# TRX.net
KiCad netlist of a schematic drawn in Altium Designer
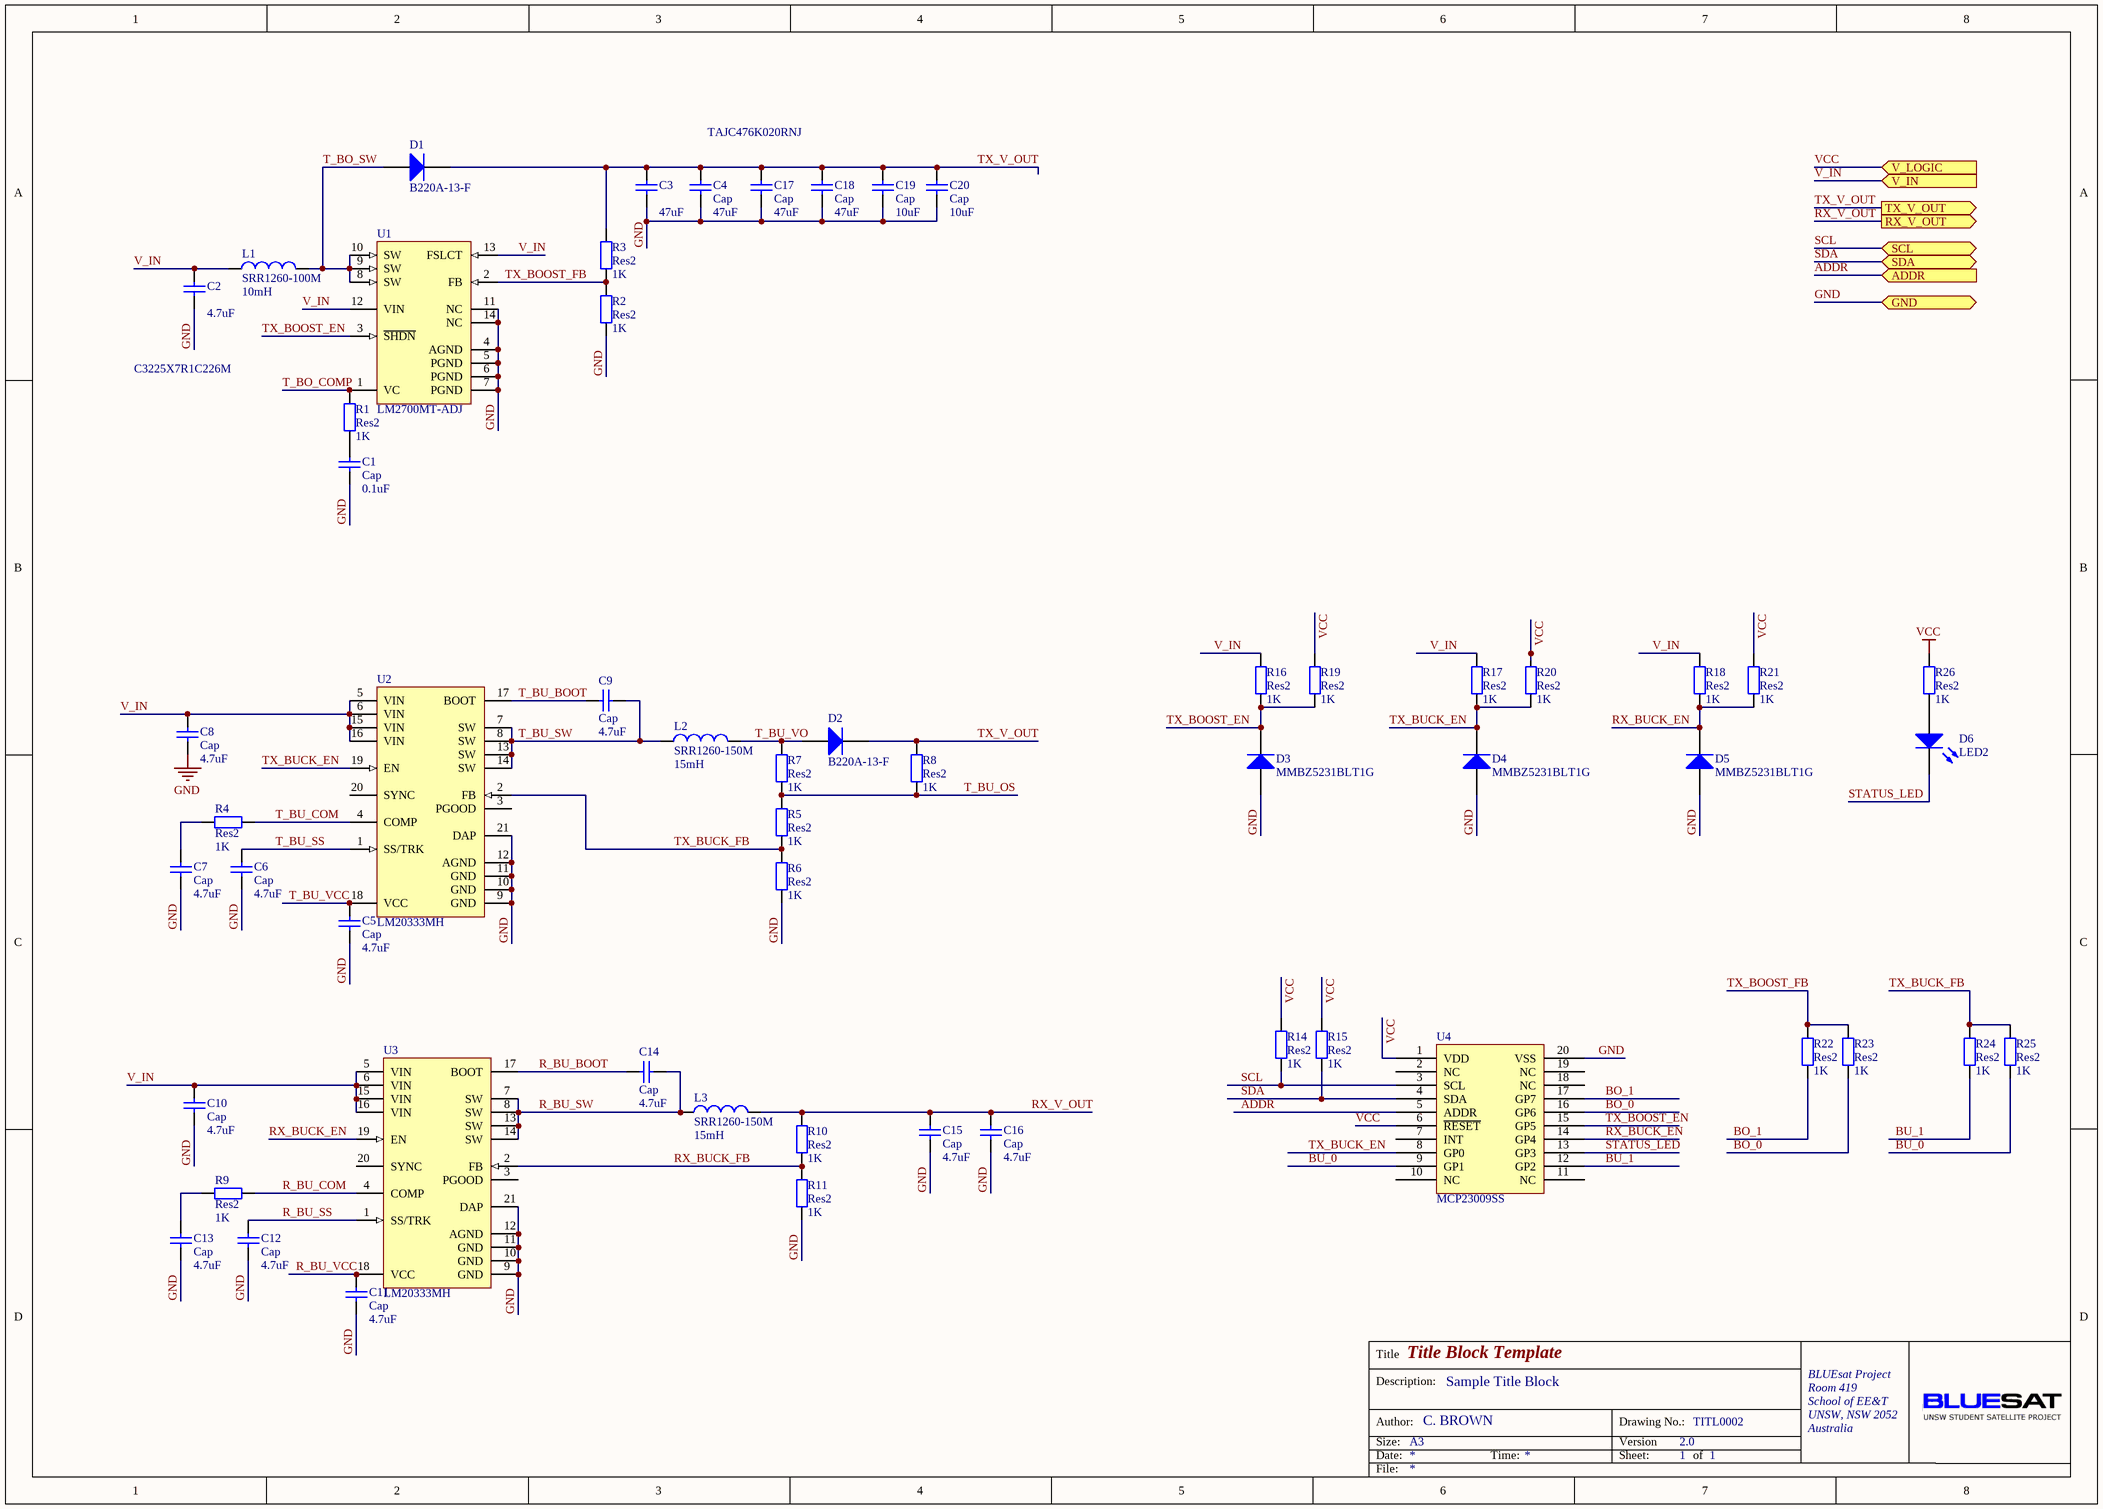
[diagram p0: TRX.SchDoc]

(export (version "E")
  (design (tool "Eeschema 10.0.6"))
  (components
    (comp (ref "C1")
      (value "Cap")
      (footprint "R0805M")
      (description "Capacitor")
      (fields (field (name "ALTIUM_VALUE") "0.1uF") (field (name "PUBLISHER") "Altium Limited"))
      (libsource (lib "Miscellaneous Devices") (part "Cap"))
    )
    (comp (ref "C2")
      (value "C3225X7R1C226M")
      (footprint "R1210M")
      (description "Capacitor")
      (fields (field (name "ALTIUM_VALUE") "4.7uF") (field (name "PUBLISHER") "Altium Limited"))
      (libsource (lib "Miscellaneous Devices") (part "Cap"))
    )
    (comp (ref "C3")
      (value "TAJC476K020RNJ")
      (footprint "TANTCASEC")
      (description "Capacitor")
      (fields (field (name "ALTIUM_VALUE") "47uF") (field (name "PUBLISHER") "Altium Limited"))
      (libsource (lib "Miscellaneous Devices") (part "Cap"))
    )
    (comp (ref "C4")
      (value "Cap")
      (footprint "TANTCASEC")
      (description "Capacitor")
      (fields (field (name "ALTIUM_VALUE") "47uF") (field (name "PUBLISHER") "Altium Limited"))
      (libsource (lib "Miscellaneous Devices") (part "Cap"))
    )
    (comp (ref "C5")
      (value "Cap")
      (footprint "R0805M")
      (description "Capacitor")
      (fields (field (name "ALTIUM_VALUE") "4.7uF") (field (name "PUBLISHER") "Altium Limited"))
      (libsource (lib "Miscellaneous Devices") (part "Cap"))
    )
    (comp (ref "C6")
      (value "Cap")
      (footprint "R0805M")
      (description "Capacitor")
      (fields (field (name "ALTIUM_VALUE") "4.7uF") (field (name "PUBLISHER") "Altium Limited"))
      (libsource (lib "Miscellaneous Devices") (part "Cap"))
    )
    (comp (ref "C7")
      (value "Cap")
      (footprint "R0805M")
      (description "Capacitor")
      (fields (field (name "ALTIUM_VALUE") "4.7uF") (field (name "PUBLISHER") "Altium Limited"))
      (libsource (lib "Miscellaneous Devices") (part "Cap"))
    )
    (comp (ref "C8")
      (value "Cap")
      (footprint "R1210M")
      (description "Capacitor")
      (fields (field (name "ALTIUM_VALUE") "4.7uF") (field (name "PUBLISHER") "Altium Limited"))
      (libsource (lib "Miscellaneous Devices") (part "Cap"))
    )
    (comp (ref "C9")
      (value "Cap")
      (footprint "R0805M")
      (description "Capacitor")
      (fields (field (name "ALTIUM_VALUE") "4.7uF") (field (name "PUBLISHER") "Altium Limited"))
      (libsource (lib "Miscellaneous Devices") (part "Cap"))
    )
    (comp (ref "C10")
      (value "Cap")
      (footprint "R1210M")
      (description "Capacitor")
      (fields (field (name "ALTIUM_VALUE") "4.7uF") (field (name "PUBLISHER") "Altium Limited"))
      (libsource (lib "Miscellaneous Devices") (part "Cap"))
    )
    (comp (ref "C11")
      (value "Cap")
      (footprint "R0805M")
      (description "Capacitor")
      (fields (field (name "ALTIUM_VALUE") "4.7uF") (field (name "PUBLISHER") "Altium Limited"))
      (libsource (lib "Miscellaneous Devices") (part "Cap"))
    )
    (comp (ref "C12")
      (value "Cap")
      (footprint "R0805M")
      (description "Capacitor")
      (fields (field (name "ALTIUM_VALUE") "4.7uF") (field (name "PUBLISHER") "Altium Limited"))
      (libsource (lib "Miscellaneous Devices") (part "Cap"))
    )
    (comp (ref "C13")
      (value "Cap")
      (footprint "R0805M")
      (description "Capacitor")
      (fields (field (name "ALTIUM_VALUE") "4.7uF") (field (name "PUBLISHER") "Altium Limited"))
      (libsource (lib "Miscellaneous Devices") (part "Cap"))
    )
    (comp (ref "C14")
      (value "Cap")
      (footprint "R0805M")
      (description "Capacitor")
      (fields (field (name "ALTIUM_VALUE") "4.7uF") (field (name "PUBLISHER") "Altium Limited"))
      (libsource (lib "Miscellaneous Devices") (part "Cap"))
    )
    (comp (ref "C15")
      (value "Cap")
      (footprint "R0805M")
      (description "Capacitor")
      (fields (field (name "ALTIUM_VALUE") "4.7uF") (field (name "PUBLISHER") "Altium Limited"))
      (libsource (lib "Miscellaneous Devices") (part "Cap"))
    )
    (comp (ref "C16")
      (value "Cap")
      (footprint "R0805M")
      (description "Capacitor")
      (fields (field (name "ALTIUM_VALUE") "4.7uF") (field (name "PUBLISHER") "Altium Limited"))
      (libsource (lib "Miscellaneous Devices") (part "Cap"))
    )
    (comp (ref "C17")
      (value "Cap")
      (footprint "TANTCASEC")
      (description "Capacitor")
      (fields (field (name "ALTIUM_VALUE") "47uF") (field (name "PUBLISHER") "Altium Limited"))
      (libsource (lib "Miscellaneous Devices") (part "Cap"))
    )
    (comp (ref "C18")
      (value "Cap")
      (footprint "TANTCASEC")
      (description "Capacitor")
      (fields (field (name "ALTIUM_VALUE") "47uF") (field (name "PUBLISHER") "Altium Limited"))
      (libsource (lib "Miscellaneous Devices") (part "Cap"))
    )
    (comp (ref "C19")
      (value "Cap")
      (footprint "R0805M")
      (description "Capacitor")
      (fields (field (name "ALTIUM_VALUE") "10uF") (field (name "PUBLISHER") "Altium Limited"))
      (libsource (lib "Miscellaneous Devices") (part "Cap"))
    )
    (comp (ref "C20")
      (value "Cap")
      (footprint "R0805M")
      (description "Capacitor")
      (fields (field (name "ALTIUM_VALUE") "10uF") (field (name "PUBLISHER") "Altium Limited"))
      (libsource (lib "Miscellaneous Devices") (part "Cap"))
    )
    (comp (ref "D1")
      (value "B220A-13-F")
      (footprint "DIODESMA")
      (description "High Conductance Fast Diode")
      (fields (field (name "PUBLISHER") "Altium Limited"))
      (libsource (lib "Miscellaneous Devices") (part "Diode 1N4148"))
    )
    (comp (ref "D2")
      (value "B220A-13-F")
      (footprint "DIODESMA")
      (description "High Conductance Fast Diode")
      (fields (field (name "PUBLISHER") "Altium Limited"))
      (libsource (lib "Miscellaneous Devices") (part "Diode 1N4148"))
    )
    (comp (ref "D3")
      (value "MMBZ5231BLT1G")
      (footprint "SOT95P240-3N")
      (description "Silicon Switching Diode for High-Speed Switching")
      (fields (field (name "PUBLISHER") "Altium Limited"))
      (libsource (lib "Miscellaneous Devices") (part "Diode BAS16"))
    )
    (comp (ref "D4")
      (value "MMBZ5231BLT1G")
      (footprint "SOT95P240-3N")
      (description "Silicon Switching Diode for High-Speed Switching")
      (fields (field (name "PUBLISHER") "Altium Limited"))
      (libsource (lib "Miscellaneous Devices") (part "Diode BAS16"))
    )
    (comp (ref "D5")
      (value "MMBZ5231BLT1G")
      (footprint "SOT95P240-3N")
      (description "Silicon Switching Diode for High-Speed Switching")
      (fields (field (name "PUBLISHER") "Altium Limited"))
      (libsource (lib "Miscellaneous Devices") (part "Diode BAS16"))
    )
    (comp (ref "D6")
      (value "LED2")
      (footprint "R0805M")
      (description "Typical RED, GREEN, YELLOW, AMBER GaAs LED")
      (fields (field (name "PUBLISHER") "Altium Limited"))
      (libsource (lib "Miscellaneous Devices") (part "LED2"))
    )
    (comp (ref "L1")
      (value "SRR1260-100M")
      (footprint "SRR1260M")
      (description "Inductor")
      (fields (field (name "ALTIUM_VALUE") "10mH") (field (name "PUBLISHER") "Altium Limited"))
      (libsource (lib "Miscellaneous Devices") (part "Inductor"))
    )
    (comp (ref "L2")
      (value "SRR1260-150M")
      (footprint "SRR1260M")
      (description "Inductor")
      (fields (field (name "ALTIUM_VALUE") "15mH") (field (name "PUBLISHER") "Altium Limited"))
      (libsource (lib "Miscellaneous Devices") (part "Inductor"))
    )
    (comp (ref "L3")
      (value "SRR1260-150M")
      (footprint "SRR1260M")
      (description "Inductor")
      (fields (field (name "ALTIUM_VALUE") "15mH") (field (name "PUBLISHER") "Altium Limited"))
      (libsource (lib "Miscellaneous Devices") (part "Inductor"))
    )
    (comp (ref "R1")
      (value "Res2")
      (footprint "R0805M")
      (description "Resistor")
      (fields (field (name "ALTIUM_VALUE") "1K") (field (name "PUBLISHER") "Altium Limited"))
      (libsource (lib "") (part "Res2_1"))
    )
    (comp (ref "R2")
      (value "Res2")
      (footprint "R0805M")
      (description "Resistor")
      (fields (field (name "ALTIUM_VALUE") "1K") (field (name "PUBLISHER") "Altium Limited"))
      (libsource (lib "") (part "Res2_1"))
    )
    (comp (ref "R3")
      (value "Res2")
      (footprint "R0805M")
      (description "Resistor")
      (fields (field (name "ALTIUM_VALUE") "1K") (field (name "PUBLISHER") "Altium Limited"))
      (libsource (lib "") (part "Res2_1"))
    )
    (comp (ref "R4")
      (value "Res2")
      (footprint "R0805M")
      (description "Resistor")
      (fields (field (name "ALTIUM_VALUE") "1K") (field (name "PUBLISHER") "Altium Limited"))
      (libsource (lib "") (part "Res2_2"))
    )
    (comp (ref "R5")
      (value "Res2")
      (footprint "R0805M")
      (description "Resistor")
      (fields (field (name "ALTIUM_VALUE") "1K") (field (name "PUBLISHER") "Altium Limited"))
      (libsource (lib "Miscellaneous Devices") (part "Res2"))
    )
    (comp (ref "R6")
      (value "Res2")
      (footprint "R0805M")
      (description "Resistor")
      (fields (field (name "ALTIUM_VALUE") "1K") (field (name "PUBLISHER") "Altium Limited"))
      (libsource (lib "Miscellaneous Devices") (part "Res2"))
    )
    (comp (ref "R7")
      (value "Res2")
      (footprint "R0805M")
      (description "Resistor")
      (fields (field (name "ALTIUM_VALUE") "1K") (field (name "PUBLISHER") "Altium Limited"))
      (libsource (lib "Miscellaneous Devices") (part "Res2"))
    )
    (comp (ref "R8")
      (value "Res2")
      (footprint "R0805M")
      (description "Resistor")
      (fields (field (name "ALTIUM_VALUE") "1K") (field (name "PUBLISHER") "Altium Limited"))
      (libsource (lib "Miscellaneous Devices") (part "Res2"))
    )
    (comp (ref "R9")
      (value "Res2")
      (footprint "R0805M")
      (description "Resistor")
      (fields (field (name "ALTIUM_VALUE") "1K") (field (name "PUBLISHER") "Altium Limited"))
      (libsource (lib "") (part "Res2_2"))
    )
    (comp (ref "R10")
      (value "Res2")
      (footprint "R0805M")
      (description "Resistor")
      (fields (field (name "ALTIUM_VALUE") "1K") (field (name "PUBLISHER") "Altium Limited"))
      (libsource (lib "") (part "Res2_1"))
    )
    (comp (ref "R11")
      (value "Res2")
      (footprint "R0805M")
      (description "Resistor")
      (fields (field (name "ALTIUM_VALUE") "1K") (field (name "PUBLISHER") "Altium Limited"))
      (libsource (lib "") (part "Res2_1"))
    )
    (comp (ref "R14")
      (value "Res2")
      (footprint "R0805M")
      (description "Resistor")
      (fields (field (name "ALTIUM_VALUE") "1K") (field (name "PUBLISHER") "Altium Limited"))
      (libsource (lib "") (part "Res2_1"))
    )
    (comp (ref "R15")
      (value "Res2")
      (footprint "R0805M")
      (description "Resistor")
      (fields (field (name "ALTIUM_VALUE") "1K") (field (name "PUBLISHER") "Altium Limited"))
      (libsource (lib "") (part "Res2_1"))
    )
    (comp (ref "R16")
      (value "Res2")
      (footprint "R0805M")
      (description "Resistor")
      (fields (field (name "ALTIUM_VALUE") "1K") (field (name "PUBLISHER") "Altium Limited"))
      (libsource (lib "") (part "Res2_1"))
    )
    (comp (ref "R17")
      (value "Res2")
      (footprint "R0805M")
      (description "Resistor")
      (fields (field (name "ALTIUM_VALUE") "1K") (field (name "PUBLISHER") "Altium Limited"))
      (libsource (lib "") (part "Res2_1"))
    )
    (comp (ref "R18")
      (value "Res2")
      (footprint "R0805M")
      (description "Resistor")
      (fields (field (name "ALTIUM_VALUE") "1K") (field (name "PUBLISHER") "Altium Limited"))
      (libsource (lib "") (part "Res2_1"))
    )
    (comp (ref "R19")
      (value "Res2")
      (footprint "R0805M")
      (description "Resistor")
      (fields (field (name "ALTIUM_VALUE") "1K") (field (name "PUBLISHER") "Altium Limited"))
      (libsource (lib "") (part "Res2_1"))
    )
    (comp (ref "R20")
      (value "Res2")
      (footprint "R0805M")
      (description "Resistor")
      (fields (field (name "ALTIUM_VALUE") "1K") (field (name "PUBLISHER") "Altium Limited"))
      (libsource (lib "") (part "Res2_1"))
    )
    (comp (ref "R21")
      (value "Res2")
      (footprint "R0805M")
      (description "Resistor")
      (fields (field (name "ALTIUM_VALUE") "1K") (field (name "PUBLISHER") "Altium Limited"))
      (libsource (lib "") (part "Res2_1"))
    )
    (comp (ref "R22")
      (value "Res2")
      (footprint "R0805M")
      (description "Resistor")
      (fields (field (name "ALTIUM_VALUE") "1K") (field (name "PUBLISHER") "Altium Limited"))
      (libsource (lib "") (part "Res2_1"))
    )
    (comp (ref "R23")
      (value "Res2")
      (footprint "R0805M")
      (description "Resistor")
      (fields (field (name "ALTIUM_VALUE") "1K") (field (name "PUBLISHER") "Altium Limited"))
      (libsource (lib "") (part "Res2_1"))
    )
    (comp (ref "R24")
      (value "Res2")
      (footprint "R0805M")
      (description "Resistor")
      (fields (field (name "ALTIUM_VALUE") "1K") (field (name "PUBLISHER") "Altium Limited"))
      (libsource (lib "") (part "Res2_1"))
    )
    (comp (ref "R25")
      (value "Res2")
      (footprint "R0805M")
      (description "Resistor")
      (fields (field (name "ALTIUM_VALUE") "1K") (field (name "PUBLISHER") "Altium Limited"))
      (libsource (lib "") (part "Res2_1"))
    )
    (comp (ref "R26")
      (value "Res2")
      (footprint "R0805M")
      (description "Resistor")
      (fields (field (name "ALTIUM_VALUE") "1K") (field (name "PUBLISHER") "Altium Limited"))
      (libsource (lib "") (part "Res2_1"))
    )
    (comp (ref "U1")
      (value "LM2700MT-ADJ")
      (footprint "MTC14_N")
      (description "600kHz/1.25MHz, 2.5A, Step-up PWM DC/DC Converter")
      (fields
        (field (name "MANUFACTURER") "National Semiconductor")
        (field (name "DIGIKEYPARTNUMBER") "LM2700MT-ADJ-ND")
        (field (name "PUBLISHER") "Altium Limited")
      )
      (libsource (lib "NSC Switcher") (part "LM2700MT-ADJ"))
    )
    (comp (ref "U2")
      (value "LM20333MH")
      (footprint "MXA20A_N")
      (description "36V, 3A PowerWise Synchronous Buck Regulator with Frequency Synchronization")
      (fields
        (field (name "MANUFACTURER") "National Semiconductor")
        (field (name "DIGIKEYPARTNUMBER") "LM20333MH-ND")
        (field (name "PUBLISHER") "Altium Limited")
      )
      (libsource (lib "NSC Switcher") (part "LM20333MH"))
    )
    (comp (ref "U3")
      (value "LM20333MH")
      (footprint "MXA20A_N")
      (description "36V, 3A PowerWise Synchronous Buck Regulator with Frequency Synchronization")
      (fields
        (field (name "MANUFACTURER") "National Semiconductor")
        (field (name "DIGIKEYPARTNUMBER") "LM20333MH-ND")
        (field (name "PUBLISHER") "Altium Limited")
      )
      (libsource (lib "NSC Switcher") (part "LM20333MH"))
    )
    (comp (ref "U4")
      (value "MCP23009SS")
      (footprint "SSOP-SS20_M")
      (libsource (lib "VarReg") (part "MCP23009SS"))
    )
  )
  (nets
    (net (code "1") (name "/ADDR") (class "Default")
      (node (ref "U4") (pin "5") (pinfunction "ADDR_5") (pintype "passive"))
    )
    (net (code "2") (name "/BO_0") (class "Default")
      (node (ref "R23") (pin "1") (pinfunction "1_1") (pintype "passive"))
      (node (ref "U4") (pin "16") (pinfunction "GP6_16") (pintype "passive"))
    )
    (net (code "3") (name "/BO_1") (class "Default")
      (node (ref "R22") (pin "1") (pinfunction "1_1") (pintype "passive"))
      (node (ref "U4") (pin "17") (pinfunction "GP7_17") (pintype "passive"))
    )
    (net (code "4") (name "/BU_0") (class "Default")
      (node (ref "R25") (pin "1") (pinfunction "1_1") (pintype "passive"))
      (node (ref "U4") (pin "9") (pinfunction "GP1_9") (pintype "passive"))
    )
    (net (code "5") (name "/BU_1") (class "Default")
      (node (ref "R24") (pin "1") (pinfunction "1_1") (pintype "passive"))
      (node (ref "U4") (pin "12") (pinfunction "GP2_12") (pintype "passive"))
    )
    (net (code "6") (name "/RX_BUCK_EN") (class "Default")
      (node (ref "D5") (pin "3") (pinfunction "K_3") (pintype "passive"))
      (node (ref "R18") (pin "1") (pinfunction "1_1") (pintype "passive"))
      (node (ref "R21") (pin "1") (pinfunction "1_1") (pintype "passive"))
      (node (ref "U3") (pin "19") (pinfunction "EN_19") (pintype "input"))
      (node (ref "U4") (pin "14") (pinfunction "GP4_14") (pintype "passive"))
    )
    (net (code "7") (name "/RX_BUCK_FB") (class "Default")
      (node (ref "R10") (pin "1") (pinfunction "1_1") (pintype "passive"))
      (node (ref "R11") (pin "2") (pinfunction "2_2") (pintype "passive"))
      (node (ref "U3") (pin "2") (pinfunction "FB_2") (pintype "input"))
    )
    (net (code "8") (name "/RX_V_OUT") (class "Default")
      (node (ref "C15") (pin "2") (pinfunction "2_2") (pintype "passive"))
      (node (ref "C16") (pin "2") (pinfunction "2_2") (pintype "passive"))
      (node (ref "L3") (pin "2") (pinfunction "2_2") (pintype "passive"))
      (node (ref "R10") (pin "2") (pinfunction "2_2") (pintype "passive"))
    )
    (net (code "9") (name "/R_BU_BOOT") (class "Default")
      (node (ref "C14") (pin "1") (pinfunction "1_1") (pintype "passive"))
      (node (ref "U3") (pin "17") (pinfunction "BOOT_17") (pintype "passive"))
    )
    (net (code "10") (name "/R_BU_COM") (class "Default")
      (node (ref "R9") (pin "1") (pinfunction "1_1") (pintype "passive"))
      (node (ref "U3") (pin "4") (pinfunction "COMP_4") (pintype "passive"))
    )
    (net (code "11") (name "/R_BU_SS") (class "Default")
      (node (ref "C12") (pin "2") (pinfunction "2_2") (pintype "passive"))
      (node (ref "U3") (pin "1") (pinfunction "SS/TRK_1") (pintype "input"))
    )
    (net (code "12") (name "/R_BU_SW") (class "Default")
      (node (ref "C14") (pin "2") (pinfunction "2_2") (pintype "passive"))
      (node (ref "L3") (pin "1") (pinfunction "1_1") (pintype "passive"))
      (node (ref "U3") (pin "13") (pinfunction "SW_13") (pintype "power_in"))
      (node (ref "U3") (pin "14") (pinfunction "SW_14") (pintype "power_in"))
      (node (ref "U3") (pin "7") (pinfunction "SW_7") (pintype "power_in"))
      (node (ref "U3") (pin "8") (pinfunction "SW_8") (pintype "power_in"))
    )
    (net (code "13") (name "/R_BU_VCC") (class "Default")
      (node (ref "C11") (pin "2") (pinfunction "2_2") (pintype "passive"))
      (node (ref "U3") (pin "18") (pinfunction "VCC_18") (pintype "power_in"))
    )
    (net (code "14") (name "/SCL") (class "Default")
      (node (ref "R14") (pin "1") (pinfunction "1_1") (pintype "passive"))
      (node (ref "U4") (pin "3") (pinfunction "SCL_3") (pintype "passive"))
    )
    (net (code "15") (name "/SDA") (class "Default")
      (node (ref "R15") (pin "1") (pinfunction "1_1") (pintype "passive"))
      (node (ref "U4") (pin "4") (pinfunction "SDA_4") (pintype "passive"))
    )
    (net (code "16") (name "/STATUS_LED") (class "Default")
      (node (ref "D6") (pin "2") (pinfunction "K_2") (pintype "passive"))
      (node (ref "U4") (pin "13") (pinfunction "GP3_13") (pintype "passive"))
    )
    (net (code "17") (name "/TX_BOOST_EN") (class "Default")
      (node (ref "D3") (pin "3") (pinfunction "K_3") (pintype "passive"))
      (node (ref "R16") (pin "1") (pinfunction "1_1") (pintype "passive"))
      (node (ref "R19") (pin "1") (pinfunction "1_1") (pintype "passive"))
      (node (ref "U1") (pin "3") (pinfunction "~{SHDN}_3") (pintype "input"))
      (node (ref "U4") (pin "15") (pinfunction "GP5_15") (pintype "passive"))
    )
    (net (code "18") (name "/TX_BOOST_FB") (class "Default")
      (node (ref "R2") (pin "2") (pinfunction "2_2") (pintype "passive"))
      (node (ref "R22") (pin "2") (pinfunction "2_2") (pintype "passive"))
      (node (ref "R23") (pin "2") (pinfunction "2_2") (pintype "passive"))
      (node (ref "R3") (pin "1") (pinfunction "1_1") (pintype "passive"))
      (node (ref "U1") (pin "2") (pinfunction "FB_2") (pintype "input"))
    )
    (net (code "19") (name "/TX_BUCK_EN") (class "Default")
      (node (ref "D4") (pin "3") (pinfunction "K_3") (pintype "passive"))
      (node (ref "R17") (pin "1") (pinfunction "1_1") (pintype "passive"))
      (node (ref "R20") (pin "1") (pinfunction "1_1") (pintype "passive"))
      (node (ref "U2") (pin "19") (pinfunction "EN_19") (pintype "input"))
      (node (ref "U4") (pin "8") (pinfunction "GP0_8") (pintype "passive"))
    )
    (net (code "20") (name "/TX_BUCK_FB") (class "Default")
      (node (ref "R24") (pin "2") (pinfunction "2_2") (pintype "passive"))
      (node (ref "R25") (pin "2") (pinfunction "2_2") (pintype "passive"))
      (node (ref "R5") (pin "2") (pinfunction "2_2") (pintype "passive"))
      (node (ref "R6") (pin "1") (pinfunction "1_1") (pintype "passive"))
      (node (ref "U2") (pin "2") (pinfunction "FB_2") (pintype "input"))
    )
    (net (code "21") (name "/TX_V_OUT") (class "Default")
      (node (ref "C17") (pin "2") (pinfunction "2_2") (pintype "passive"))
      (node (ref "C18") (pin "2") (pinfunction "2_2") (pintype "passive"))
      (node (ref "C19") (pin "2") (pinfunction "2_2") (pintype "passive"))
      (node (ref "C20") (pin "2") (pinfunction "2_2") (pintype "passive"))
      (node (ref "C3") (pin "2") (pinfunction "2_2") (pintype "passive"))
      (node (ref "C4") (pin "2") (pinfunction "2_2") (pintype "passive"))
      (node (ref "D1") (pin "2") (pinfunction "K_2") (pintype "passive"))
      (node (ref "D2") (pin "2") (pinfunction "K_2") (pintype "passive"))
      (node (ref "R3") (pin "2") (pinfunction "2_2") (pintype "passive"))
      (node (ref "R8") (pin "1") (pinfunction "1_1") (pintype "passive"))
    )
    (net (code "22") (name "/T_BO_COMP") (class "Default")
      (node (ref "R1") (pin "2") (pinfunction "2_2") (pintype "passive"))
      (node (ref "U1") (pin "1") (pinfunction "VC_1") (pintype "power_in"))
    )
    (net (code "23") (name "/T_BO_SW") (class "Default")
      (node (ref "D1") (pin "1") (pinfunction "A_1") (pintype "passive"))
      (node (ref "L1") (pin "2") (pinfunction "2_2") (pintype "passive"))
      (node (ref "U1") (pin "10") (pinfunction "SW_10") (pintype "input"))
      (node (ref "U1") (pin "8") (pinfunction "SW_8") (pintype "input"))
      (node (ref "U1") (pin "9") (pinfunction "SW_9") (pintype "input"))
    )
    (net (code "24") (name "/T_BU_BOOT") (class "Default")
      (node (ref "C9") (pin "2") (pinfunction "2_2") (pintype "passive"))
      (node (ref "U2") (pin "17") (pinfunction "BOOT_17") (pintype "passive"))
    )
    (net (code "25") (name "/T_BU_COM") (class "Default")
      (node (ref "R4") (pin "1") (pinfunction "1_1") (pintype "passive"))
      (node (ref "U2") (pin "4") (pinfunction "COMP_4") (pintype "passive"))
    )
    (net (code "26") (name "/T_BU_OS") (class "Default")
      (node (ref "R5") (pin "1") (pinfunction "1_1") (pintype "passive"))
      (node (ref "R7") (pin "2") (pinfunction "2_2") (pintype "passive"))
      (node (ref "R8") (pin "2") (pinfunction "2_2") (pintype "passive"))
    )
    (net (code "27") (name "/T_BU_SS") (class "Default")
      (node (ref "C6") (pin "2") (pinfunction "2_2") (pintype "passive"))
      (node (ref "U2") (pin "1") (pinfunction "SS/TRK_1") (pintype "input"))
    )
    (net (code "28") (name "/T_BU_SW") (class "Default")
      (node (ref "C9") (pin "1") (pinfunction "1_1") (pintype "passive"))
      (node (ref "L2") (pin "1") (pinfunction "1_1") (pintype "passive"))
      (node (ref "U2") (pin "13") (pinfunction "SW_13") (pintype "power_in"))
      (node (ref "U2") (pin "14") (pinfunction "SW_14") (pintype "power_in"))
      (node (ref "U2") (pin "7") (pinfunction "SW_7") (pintype "power_in"))
      (node (ref "U2") (pin "8") (pinfunction "SW_8") (pintype "power_in"))
    )
    (net (code "29") (name "/T_BU_VCC") (class "Default")
      (node (ref "C5") (pin "2") (pinfunction "2_2") (pintype "passive"))
      (node (ref "U2") (pin "18") (pinfunction "VCC_18") (pintype "power_in"))
    )
    (net (code "30") (name "/T_BU_VO") (class "Default")
      (node (ref "D2") (pin "1") (pinfunction "A_1") (pintype "passive"))
      (node (ref "L2") (pin "2") (pinfunction "2_2") (pintype "passive"))
      (node (ref "R7") (pin "1") (pinfunction "1_1") (pintype "passive"))
    )
    (net (code "31") (name "/V_IN") (class "Default")
      (node (ref "C10") (pin "2") (pinfunction "2_2") (pintype "passive"))
      (node (ref "C2") (pin "2") (pinfunction "2_2") (pintype "passive"))
      (node (ref "C8") (pin "2") (pinfunction "2_2") (pintype "passive"))
      (node (ref "L1") (pin "1") (pinfunction "1_1") (pintype "passive"))
      (node (ref "R16") (pin "2") (pinfunction "2_2") (pintype "passive"))
      (node (ref "R17") (pin "2") (pinfunction "2_2") (pintype "passive"))
      (node (ref "R18") (pin "2") (pinfunction "2_2") (pintype "passive"))
      (node (ref "U1") (pin "12") (pinfunction "VIN_12") (pintype "passive"))
      (node (ref "U1") (pin "13") (pinfunction "FSLCT_13") (pintype "input"))
      (node (ref "U2") (pin "15") (pinfunction "VIN_15") (pintype "passive"))
      (node (ref "U2") (pin "16") (pinfunction "VIN_16") (pintype "passive"))
      (node (ref "U2") (pin "5") (pinfunction "VIN_5") (pintype "passive"))
      (node (ref "U2") (pin "6") (pinfunction "VIN_6") (pintype "passive"))
      (node (ref "U3") (pin "15") (pinfunction "VIN_15") (pintype "passive"))
      (node (ref "U3") (pin "16") (pinfunction "VIN_16") (pintype "passive"))
      (node (ref "U3") (pin "5") (pinfunction "VIN_5") (pintype "passive"))
      (node (ref "U3") (pin "6") (pinfunction "VIN_6") (pintype "passive"))
    )
    (net (code "32") (name "GND") (class "Default")
      (node (ref "C1") (pin "1") (pinfunction "1_1") (pintype "passive"))
      (node (ref "C10") (pin "1") (pinfunction "1_1") (pintype "passive"))
      (node (ref "C11") (pin "1") (pinfunction "1_1") (pintype "passive"))
      (node (ref "C12") (pin "1") (pinfunction "1_1") (pintype "passive"))
      (node (ref "C13") (pin "1") (pinfunction "1_1") (pintype "passive"))
      (node (ref "C15") (pin "1") (pinfunction "1_1") (pintype "passive"))
      (node (ref "C16") (pin "1") (pinfunction "1_1") (pintype "passive"))
      (node (ref "C17") (pin "1") (pinfunction "1_1") (pintype "passive"))
      (node (ref "C18") (pin "1") (pinfunction "1_1") (pintype "passive"))
      (node (ref "C19") (pin "1") (pinfunction "1_1") (pintype "passive"))
      (node (ref "C2") (pin "1") (pinfunction "1_1") (pintype "passive"))
      (node (ref "C20") (pin "1") (pinfunction "1_1") (pintype "passive"))
      (node (ref "C3") (pin "1") (pinfunction "1_1") (pintype "passive"))
      (node (ref "C4") (pin "1") (pinfunction "1_1") (pintype "passive"))
      (node (ref "C5") (pin "1") (pinfunction "1_1") (pintype "passive"))
      (node (ref "C6") (pin "1") (pinfunction "1_1") (pintype "passive"))
      (node (ref "C7") (pin "1") (pinfunction "1_1") (pintype "passive"))
      (node (ref "C8") (pin "1") (pinfunction "1_1") (pintype "passive"))
      (node (ref "D3") (pin "1") (pinfunction "A_1") (pintype "passive"))
      (node (ref "D4") (pin "1") (pinfunction "A_1") (pintype "passive"))
      (node (ref "D5") (pin "1") (pinfunction "A_1") (pintype "passive"))
      (node (ref "R11") (pin "1") (pinfunction "1_1") (pintype "passive"))
      (node (ref "R2") (pin "1") (pinfunction "1_1") (pintype "passive"))
      (node (ref "R6") (pin "2") (pinfunction "2_2") (pintype "passive"))
      (node (ref "U1") (pin "11") (pinfunction "NC_11") (pintype "passive"))
      (node (ref "U1") (pin "14") (pinfunction "NC_14") (pintype "passive"))
      (node (ref "U1") (pin "4") (pinfunction "AGND_4") (pintype "power_in"))
      (node (ref "U1") (pin "5") (pinfunction "PGND_5") (pintype "power_in"))
      (node (ref "U1") (pin "6") (pinfunction "PGND_6") (pintype "power_in"))
      (node (ref "U1") (pin "7") (pinfunction "PGND_7") (pintype "power_in"))
      (node (ref "U2") (pin "10") (pinfunction "GND_10") (pintype "power_in"))
      (node (ref "U2") (pin "11") (pinfunction "GND_11") (pintype "power_in"))
      (node (ref "U2") (pin "12") (pinfunction "AGND_12") (pintype "power_in"))
      (node (ref "U2") (pin "21") (pinfunction "DAP_21") (pintype "power_in"))
      (node (ref "U2") (pin "9") (pinfunction "GND_9") (pintype "power_in"))
      (node (ref "U3") (pin "10") (pinfunction "GND_10") (pintype "power_in"))
      (node (ref "U3") (pin "11") (pinfunction "GND_11") (pintype "power_in"))
      (node (ref "U3") (pin "12") (pinfunction "AGND_12") (pintype "power_in"))
      (node (ref "U3") (pin "21") (pinfunction "DAP_21") (pintype "power_in"))
      (node (ref "U3") (pin "9") (pinfunction "GND_9") (pintype "power_in"))
      (node (ref "U4") (pin "20") (pinfunction "VSS_20") (pintype "passive"))
    )
    (net (code "33") (name "Net-(C1-Pad2)") (class "Default")
      (node (ref "C1") (pin "2") (pinfunction "2_2") (pintype "passive"))
      (node (ref "R1") (pin "1") (pinfunction "1_1") (pintype "passive"))
    )
    (net (code "34") (name "Net-(C7-Pad2)") (class "Default")
      (node (ref "C7") (pin "2") (pinfunction "2_2") (pintype "passive"))
      (node (ref "R4") (pin "2") (pinfunction "2_2") (pintype "passive"))
    )
    (net (code "35") (name "Net-(C13-Pad2)") (class "Default")
      (node (ref "C13") (pin "2") (pinfunction "2_2") (pintype "passive"))
      (node (ref "R9") (pin "2") (pinfunction "2_2") (pintype "passive"))
    )
    (net (code "36") (name "Net-(D6-A)") (class "Default")
      (node (ref "D6") (pin "1") (pinfunction "A_1") (pintype "passive"))
      (node (ref "R26") (pin "1") (pinfunction "1_1") (pintype "passive"))
    )
    (net (code "37") (name "VCC") (class "Default")
      (node (ref "R14") (pin "2") (pinfunction "2_2") (pintype "passive"))
      (node (ref "R15") (pin "2") (pinfunction "2_2") (pintype "passive"))
      (node (ref "R19") (pin "2") (pinfunction "2_2") (pintype "passive"))
      (node (ref "R20") (pin "2") (pinfunction "2_2") (pintype "passive"))
      (node (ref "R21") (pin "2") (pinfunction "2_2") (pintype "passive"))
      (node (ref "R26") (pin "2") (pinfunction "2_2") (pintype "passive"))
      (node (ref "U4") (pin "1") (pinfunction "VDD_1") (pintype "passive"))
      (node (ref "U4") (pin "6") (pinfunction "~{RESET}_6") (pintype "passive"))
    )
    (net (code "38") (name "unconnected-(U2-PGOOD-Pad3)") (class "Default")
      (node (ref "U2") (pin "3") (pinfunction "PGOOD_3") (pintype "open_collector"))
    )
    (net (code "39") (name "unconnected-(U2-SYNC-Pad20)") (class "Default")
      (node (ref "U2") (pin "20") (pinfunction "SYNC_20") (pintype "passive"))
    )
    (net (code "40") (name "unconnected-(U3-PGOOD-Pad3)") (class "Default")
      (node (ref "U3") (pin "3") (pinfunction "PGOOD_3") (pintype "open_collector"))
    )
    (net (code "41") (name "unconnected-(U3-SYNC-Pad20)") (class "Default")
      (node (ref "U3") (pin "20") (pinfunction "SYNC_20") (pintype "passive"))
    )
    (net (code "42") (name "unconnected-(U4-INT-Pad7)") (class "Default")
      (node (ref "U4") (pin "7") (pinfunction "INT_7") (pintype "passive"))
    )
    (net (code "43") (name "unconnected-(U4-NC-Pad2)") (class "Default")
      (node (ref "U4") (pin "2") (pinfunction "NC_2") (pintype "passive"))
    )
    (net (code "44") (name "unconnected-(U4-NC-Pad10)") (class "Default")
      (node (ref "U4") (pin "10") (pinfunction "NC_10") (pintype "passive"))
    )
    (net (code "45") (name "unconnected-(U4-NC-Pad11)") (class "Default")
      (node (ref "U4") (pin "11") (pinfunction "NC_11") (pintype "passive"))
    )
    (net (code "46") (name "unconnected-(U4-NC-Pad18)") (class "Default")
      (node (ref "U4") (pin "18") (pinfunction "NC_18") (pintype "passive"))
    )
    (net (code "47") (name "unconnected-(U4-NC-Pad19)") (class "Default")
      (node (ref "U4") (pin "19") (pinfunction "NC_19") (pintype "passive"))
    )
  )
)
